# Peripherials.net
KiCad netlist of a schematic drawn in Altium Designer
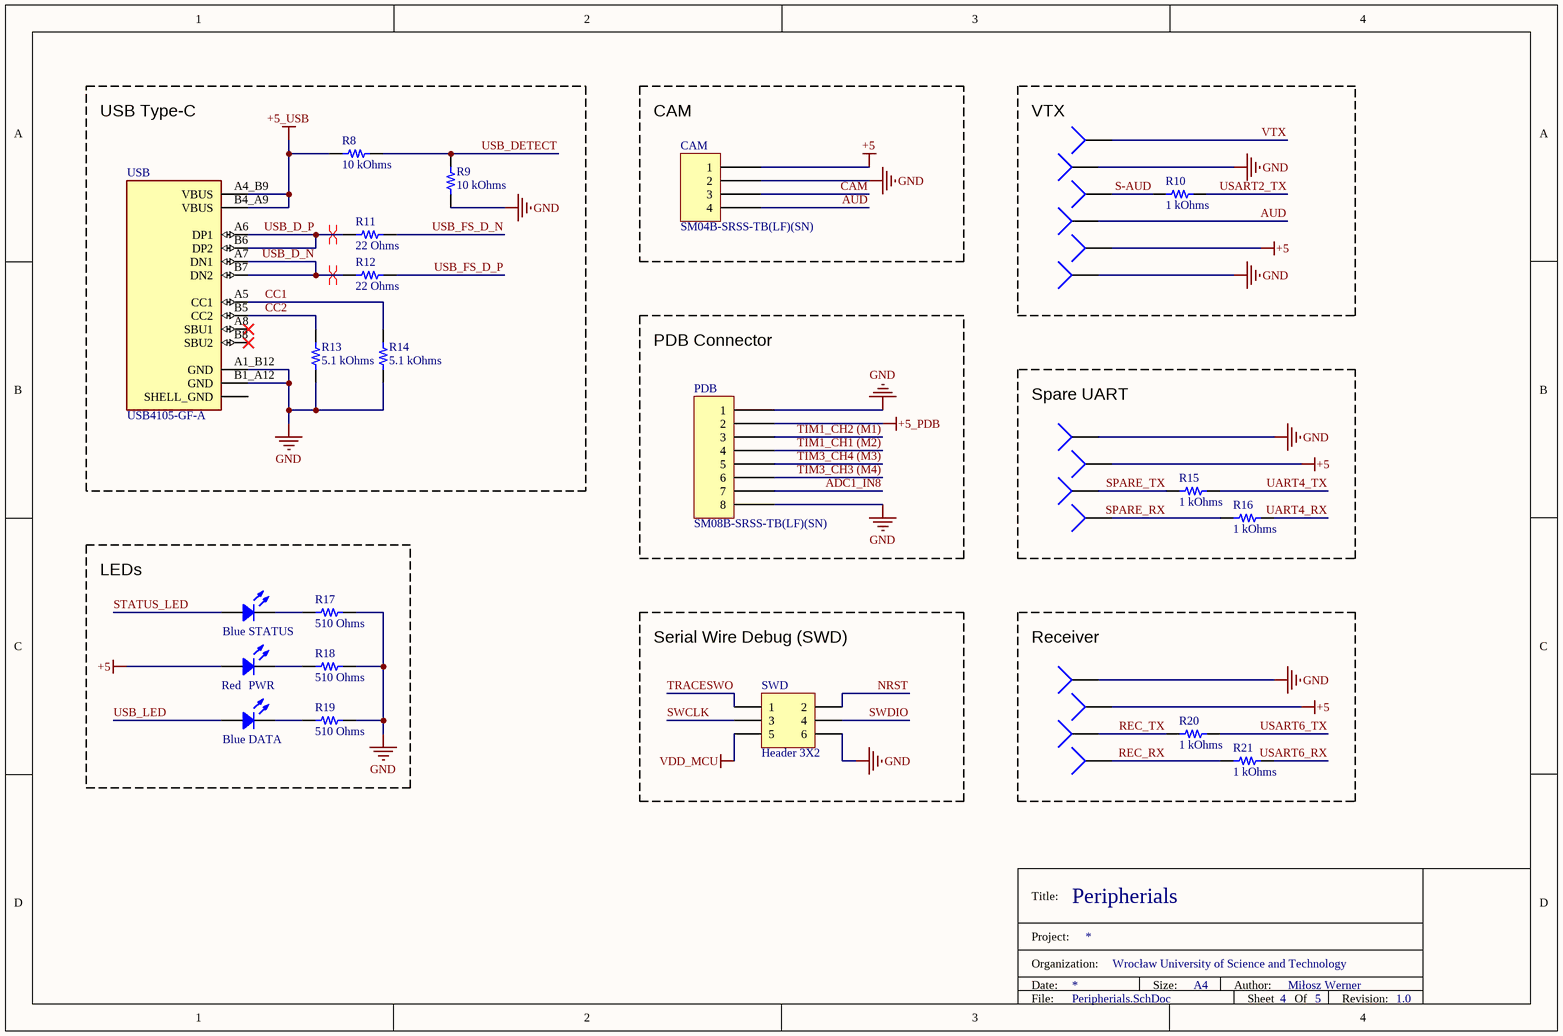
[diagram p0: Peripherials.SchDoc]

(export (version "E")
  (design (tool "Eeschema 10.0.6"))
  (components
    (comp (ref "CAM")
      (value "SM04B-SRSS-TB(LF)(SN)")
      (footprint "JST SM04B-SRSS-TB")
      (description "CONN HEADER SMD R/A 4POS 1MM")
      (fields (field (name "MANUFACTURER") "JST Sales America Inc."))
      (libsource (lib "Celestial Altium Library - altium_library") (part "4 Pin"))
    )
    (comp (ref "DATA")
      (value "Blue")
      (footprint "LED 0603_1608 BLUE")
      (description "LED BLUE CLEAR 0603 SMD")
      (fields (field (name "PART NUMBER") "QBLP601-IB") (field (name "MANUFACTURER") "QT Brightek (QTB)"))
      (libsource (lib "Celestial Altium Library - altium_library") (part "LED"))
    )
    (comp (ref "J1")
      (value "Socket")
      (footprint "PIN1")
      (fields (field (name "PUBLISHER") "Altium Limited"))
      (libsource (lib "Miscellaneous Connectors") (part "Socket"))
    )
    (comp (ref "J2")
      (value "Socket")
      (footprint "PIN1")
      (fields (field (name "PUBLISHER") "Altium Limited"))
      (libsource (lib "Miscellaneous Connectors") (part "Socket"))
    )
    (comp (ref "J3")
      (value "Socket")
      (footprint "PIN1")
      (fields (field (name "PUBLISHER") "Altium Limited"))
      (libsource (lib "Miscellaneous Connectors") (part "Socket"))
    )
    (comp (ref "J4")
      (value "Socket")
      (footprint "PIN1")
      (fields (field (name "PUBLISHER") "Altium Limited"))
      (libsource (lib "Miscellaneous Connectors") (part "Socket"))
    )
    (comp (ref "J5")
      (value "Socket")
      (footprint "PIN1")
      (fields (field (name "PUBLISHER") "Altium Limited"))
      (libsource (lib "Miscellaneous Connectors") (part "Socket"))
    )
    (comp (ref "J6")
      (value "Socket")
      (footprint "PIN1")
      (fields (field (name "PUBLISHER") "Altium Limited"))
      (libsource (lib "Miscellaneous Connectors") (part "Socket"))
    )
    (comp (ref "J7")
      (value "Socket")
      (footprint "PIN1")
      (fields (field (name "PUBLISHER") "Altium Limited"))
      (libsource (lib "Miscellaneous Connectors") (part "Socket"))
    )
    (comp (ref "J8")
      (value "Socket")
      (footprint "PIN1")
      (fields (field (name "PUBLISHER") "Altium Limited"))
      (libsource (lib "Miscellaneous Connectors") (part "Socket"))
    )
    (comp (ref "J9")
      (value "Socket")
      (footprint "PIN1")
      (fields (field (name "PUBLISHER") "Altium Limited"))
      (libsource (lib "Miscellaneous Connectors") (part "Socket"))
    )
    (comp (ref "J10")
      (value "Socket")
      (footprint "PIN1")
      (fields (field (name "PUBLISHER") "Altium Limited"))
      (libsource (lib "Miscellaneous Connectors") (part "Socket"))
    )
    (comp (ref "J11")
      (value "Socket")
      (footprint "PIN1")
      (fields (field (name "PUBLISHER") "Altium Limited"))
      (libsource (lib "Miscellaneous Connectors") (part "Socket"))
    )
    (comp (ref "J12")
      (value "Socket")
      (footprint "PIN1")
      (fields (field (name "PUBLISHER") "Altium Limited"))
      (libsource (lib "Miscellaneous Connectors") (part "Socket"))
    )
    (comp (ref "J13")
      (value "Socket")
      (footprint "PIN1")
      (fields (field (name "PUBLISHER") "Altium Limited"))
      (libsource (lib "Miscellaneous Connectors") (part "Socket"))
    )
    (comp (ref "J14")
      (value "Socket")
      (footprint "PIN1")
      (fields (field (name "PUBLISHER") "Altium Limited"))
      (libsource (lib "Miscellaneous Connectors") (part "Socket"))
    )
    (comp (ref "PDB")
      (value "SM08B-SRSS-TB(LF)(SN)")
      (footprint "JST SM08B-SRSS-TB")
      (description "CONN HEADER SMD R/A 8POS 1MM")
      (fields (field (name "MANUFACTURER") "JST Sales America Inc."))
      (libsource (lib "Celestial Altium Library - altium_library") (part "8 Pin"))
    )
    (comp (ref "PWR")
      (value "Red")
      (footprint "LED 0603_1608 RED")
      (description "LED RED CLEAR 0603 SMD")
      (fields (field (name "PART NUMBER") "QBLP601-R") (field (name "MANUFACTURER") "QT Brightek (QTB)"))
      (libsource (lib "Celestial Altium Library - altium_library") (part "LED"))
    )
    (comp (ref "R8")
      (value "10 kOhms")
      (footprint "RES 0603_1608")
      (description "RES 10K OHM 0.1% 1/5W 0603")
      (fields
        (field (name "PART NUMBER") "RS73F1JTTD1002B")
        (field (name "MANUFACTURER") "KOA Speer Electronics, Inc.")
      )
      (libsource (lib "Celestial Altium Library - altium_library") (part "Resistor"))
    )
    (comp (ref "R9")
      (value "10 kOhms")
      (footprint "RES 0603_1608")
      (description "RES 10K OHM 0.1% 1/5W 0603")
      (fields
        (field (name "PART NUMBER") "RS73F1JTTD1002B")
        (field (name "MANUFACTURER") "KOA Speer Electronics, Inc.")
      )
      (libsource (lib "Celestial Altium Library - altium_library") (part "Resistor"))
    )
    (comp (ref "R10")
      (value "1 kOhms")
      (footprint "RES 0603_1608")
      (description "RES 1K OHM 1% 1/5W 0603")
      (fields
        (field (name "PART NUMBER") "SG73S1JTTD1001F")
        (field (name "MANUFACTURER") "KOA Speer Electronics, Inc.")
      )
      (libsource (lib "Celestial Altium Library - altium_library") (part "Resistor"))
    )
    (comp (ref "R11")
      (value "22 Ohms")
      (footprint "RES 0603_1608")
      (description "RES 22 OHM 1% 1/10W 0603")
      (fields
        (field (name "PART NUMBER") "RMCF0603FT22R0")
        (field (name "MANUFACTURER") "Stackpole Electronics Inc")
      )
      (libsource (lib "Celestial Altium Library - altium_library") (part "Resistor"))
    )
    (comp (ref "R12")
      (value "22 Ohms")
      (footprint "RES 0603_1608")
      (description "RES 22 OHM 1% 1/10W 0603")
      (fields
        (field (name "PART NUMBER") "RMCF0603FT22R0")
        (field (name "MANUFACTURER") "Stackpole Electronics Inc")
      )
      (libsource (lib "Celestial Altium Library - altium_library") (part "Resistor"))
    )
    (comp (ref "R13")
      (value "5.1 kOhms")
      (footprint "RES 0603_1608")
      (description "RES 5.1 KOHM 1% 1/10W 0603")
      (fields
        (field (name "PART NUMBER") "RK73H1JRTTD5101F")
        (field (name "MANUFACTURER") "KOA Speer Electronics, Inc.")
      )
      (libsource (lib "Celestial Altium Library - altium_library") (part "Resistor"))
    )
    (comp (ref "R14")
      (value "5.1 kOhms")
      (footprint "RES 0603_1608")
      (description "RES 5.1 KOHM 1% 1/10W 0603")
      (fields
        (field (name "PART NUMBER") "RK73H1JRTTD5101F")
        (field (name "MANUFACTURER") "KOA Speer Electronics, Inc.")
      )
      (libsource (lib "Celestial Altium Library - altium_library") (part "Resistor"))
    )
    (comp (ref "R15")
      (value "1 kOhms")
      (footprint "RES 0603_1608")
      (description "RES 1K OHM 1% 1/5W 0603")
      (fields
        (field (name "PART NUMBER") "SG73S1JTTD1001F")
        (field (name "MANUFACTURER") "KOA Speer Electronics, Inc.")
      )
      (libsource (lib "Celestial Altium Library - altium_library") (part "Resistor"))
    )
    (comp (ref "R16")
      (value "1 kOhms")
      (footprint "RES 0603_1608")
      (description "RES 1K OHM 1% 1/5W 0603")
      (fields
        (field (name "PART NUMBER") "SG73S1JTTD1001F")
        (field (name "MANUFACTURER") "KOA Speer Electronics, Inc.")
      )
      (libsource (lib "Celestial Altium Library - altium_library") (part "Resistor"))
    )
    (comp (ref "R17")
      (value "510 Ohms")
      (footprint "RES 0603_1608")
      (description "RES 510 OHM 5% 1/8W 0603")
      (fields
        (field (name "PART NUMBER") "RK73B1JTTD511J")
        (field (name "MANUFACTURER") "KOA Speer Electronics, Inc.")
      )
      (libsource (lib "Celestial Altium Library - altium_library") (part "Resistor"))
    )
    (comp (ref "R18")
      (value "510 Ohms")
      (footprint "RES 0603_1608")
      (description "RES 510 OHM 5% 1/8W 0603")
      (fields
        (field (name "PART NUMBER") "RK73B1JTTD511J")
        (field (name "MANUFACTURER") "KOA Speer Electronics, Inc.")
      )
      (libsource (lib "Celestial Altium Library - altium_library") (part "Resistor"))
    )
    (comp (ref "R19")
      (value "510 Ohms")
      (footprint "RES 0603_1608")
      (description "RES 510 OHM 5% 1/8W 0603")
      (fields
        (field (name "PART NUMBER") "RK73B1JTTD511J")
        (field (name "MANUFACTURER") "KOA Speer Electronics, Inc.")
      )
      (libsource (lib "Celestial Altium Library - altium_library") (part "Resistor"))
    )
    (comp (ref "R20")
      (value "1 kOhms")
      (footprint "RES 0603_1608")
      (description "RES 1K OHM 1% 1/5W 0603")
      (fields
        (field (name "PART NUMBER") "SG73S1JTTD1001F")
        (field (name "MANUFACTURER") "KOA Speer Electronics, Inc.")
      )
      (libsource (lib "Celestial Altium Library - altium_library") (part "Resistor"))
    )
    (comp (ref "R21")
      (value "1 kOhms")
      (footprint "RES 0603_1608")
      (description "RES 1K OHM 1% 1/5W 0603")
      (fields
        (field (name "PART NUMBER") "SG73S1JTTD1001F")
        (field (name "MANUFACTURER") "KOA Speer Electronics, Inc.")
      )
      (libsource (lib "Celestial Altium Library - altium_library") (part "Resistor"))
    )
    (comp (ref "STATUS")
      (value "Blue")
      (footprint "LED 0603_1608 BLUE")
      (description "LED BLUE CLEAR 0603 SMD")
      (fields (field (name "PART NUMBER") "QBLP601-IB") (field (name "MANUFACTURER") "QT Brightek (QTB)"))
      (libsource (lib "Celestial Altium Library - altium_library") (part "LED"))
    )
    (comp (ref "SWD")
      (value "Header 3X2")
      (footprint "HDR2X3")
      (description "Header, 3-Pin, Dual row")
      (fields (field (name "PUBLISHER") "Altium Limited"))
      (libsource (lib "Miscellaneous Connectors") (part "Header 3X2"))
    )
    (comp (ref "USB")
      (value "USB4105-GF-A")
      (footprint "USB4105-GF-A:GCT_USB4105-GF-A")
      (fields (field (name "MF") "{'manufacturer': u'GCT'}"))
      (libsource (lib "USB4105-GF-A") (part "USB4105-GF-A"))
    )
  )
  (nets
    (net (code "1") (name "+5") (class "Default")
      (node (ref "CAM") (pin "1") (pinfunction "1_1") (pintype "passive"))
      (node (ref "J12") (pin "1") (pinfunction "1_1") (pintype "passive"))
      (node (ref "J5") (pin "1") (pinfunction "1_1") (pintype "passive"))
      (node (ref "J8") (pin "1") (pinfunction "1_1") (pintype "passive"))
      (node (ref "PWR") (pin "1") (pinfunction "1_1") (pintype "passive"))
    )
    (net (code "2") (name "+5_PDB") (class "Default")
      (node (ref "PDB") (pin "2") (pinfunction "2_2") (pintype "passive"))
    )
    (net (code "3") (name "+5_USB") (class "Default")
      (node (ref "R8") (pin "2") (pinfunction "2_2") (pintype "passive"))
      (node (ref "USB") (pin "A4_B9") (pinfunction "VBUS_A4_B9") (pintype "power_in"))
      (node (ref "USB") (pin "B4_A9") (pinfunction "VBUS_B4_A9") (pintype "power_in"))
    )
    (net (code "4") (name "/ADC1_IN8") (class "Default")
      (node (ref "PDB") (pin "7") (pinfunction "7_7") (pintype "passive"))
    )
    (net (code "5") (name "/AUD") (class "Default")
      (node (ref "CAM") (pin "4") (pinfunction "4_4") (pintype "passive"))
      (node (ref "J4") (pin "1") (pinfunction "1_1") (pintype "passive"))
    )
    (net (code "6") (name "/CAM") (class "Default")
      (node (ref "CAM") (pin "3") (pinfunction "3_3") (pintype "passive"))
    )
    (net (code "7") (name "/CC1") (class "Default")
      (node (ref "R14") (pin "1") (pinfunction "1_1") (pintype "passive"))
      (node (ref "USB") (pin "A5") (pinfunction "CC1_A5") (pintype "bidirectional"))
    )
    (net (code "8") (name "/CC2") (class "Default")
      (node (ref "R13") (pin "1") (pinfunction "1_1") (pintype "passive"))
      (node (ref "USB") (pin "B5") (pinfunction "CC2_B5") (pintype "bidirectional"))
    )
    (net (code "9") (name "/NRST") (class "Default")
      (node (ref "SWD") (pin "2") (pinfunction "2_2") (pintype "passive"))
    )
    (net (code "10") (name "/REC_RX") (class "Default")
      (node (ref "J14") (pin "1") (pinfunction "1_1") (pintype "passive"))
      (node (ref "R21") (pin "1") (pinfunction "1_1") (pintype "passive"))
    )
    (net (code "11") (name "/REC_TX") (class "Default")
      (node (ref "J13") (pin "1") (pinfunction "1_1") (pintype "passive"))
      (node (ref "R20") (pin "1") (pinfunction "1_1") (pintype "passive"))
    )
    (net (code "12") (name "/S-AUD") (class "Default")
      (node (ref "J3") (pin "1") (pinfunction "1_1") (pintype "passive"))
      (node (ref "R10") (pin "1") (pinfunction "1_1") (pintype "passive"))
    )
    (net (code "13") (name "/SPARE_RX") (class "Default")
      (node (ref "J10") (pin "1") (pinfunction "1_1") (pintype "passive"))
      (node (ref "R16") (pin "1") (pinfunction "1_1") (pintype "passive"))
    )
    (net (code "14") (name "/SPARE_TX") (class "Default")
      (node (ref "J9") (pin "1") (pinfunction "1_1") (pintype "passive"))
      (node (ref "R15") (pin "1") (pinfunction "1_1") (pintype "passive"))
    )
    (net (code "15") (name "/STATUS_LED") (class "Default")
      (node (ref "STATUS") (pin "1") (pinfunction "1_1") (pintype "passive"))
    )
    (net (code "16") (name "/SWCLK") (class "Default")
      (node (ref "SWD") (pin "3") (pinfunction "3_3") (pintype "passive"))
    )
    (net (code "17") (name "/SWDIO") (class "Default")
      (node (ref "SWD") (pin "4") (pinfunction "4_4") (pintype "passive"))
    )
    (net (code "18") (name "/TIM1_CH1 (M2)") (class "Default")
      (node (ref "PDB") (pin "4") (pinfunction "4_4") (pintype "passive"))
    )
    (net (code "19") (name "/TIM1_CH2 (M1)") (class "Default")
      (node (ref "PDB") (pin "3") (pinfunction "3_3") (pintype "passive"))
    )
    (net (code "20") (name "/TIM3_CH3 (M4)") (class "Default")
      (node (ref "PDB") (pin "6") (pinfunction "6_6") (pintype "passive"))
    )
    (net (code "21") (name "/TIM3_CH4 (M3)") (class "Default")
      (node (ref "PDB") (pin "5") (pinfunction "5_5") (pintype "passive"))
    )
    (net (code "22") (name "/TRACESWO") (class "Default")
      (node (ref "SWD") (pin "1") (pinfunction "1_1") (pintype "passive"))
    )
    (net (code "23") (name "/UART4_RX") (class "Default")
      (node (ref "R16") (pin "2") (pinfunction "2_2") (pintype "passive"))
    )
    (net (code "24") (name "/UART4_TX") (class "Default")
      (node (ref "R15") (pin "2") (pinfunction "2_2") (pintype "passive"))
    )
    (net (code "25") (name "/USART2_TX") (class "Default")
      (node (ref "R10") (pin "2") (pinfunction "2_2") (pintype "passive"))
    )
    (net (code "26") (name "/USART6_RX") (class "Default")
      (node (ref "R21") (pin "2") (pinfunction "2_2") (pintype "passive"))
    )
    (net (code "27") (name "/USART6_TX") (class "Default")
      (node (ref "R20") (pin "2") (pinfunction "2_2") (pintype "passive"))
    )
    (net (code "28") (name "/USB_DETECT") (class "Default")
      (node (ref "R8") (pin "1") (pinfunction "1_1") (pintype "passive"))
      (node (ref "R9") (pin "1") (pinfunction "1_1") (pintype "passive"))
    )
    (net (code "29") (name "/USB_D_N") (class "Default")
      (node (ref "R12") (pin "1") (pinfunction "1_1") (pintype "passive"))
      (node (ref "USB") (pin "A7") (pinfunction "DN1_A7") (pintype "bidirectional"))
      (node (ref "USB") (pin "B7") (pinfunction "DN2_B7") (pintype "bidirectional"))
    )
    (net (code "30") (name "/USB_D_P") (class "Default")
      (node (ref "R11") (pin "1") (pinfunction "1_1") (pintype "passive"))
      (node (ref "USB") (pin "A6") (pinfunction "DP1_A6") (pintype "bidirectional"))
      (node (ref "USB") (pin "B6") (pinfunction "DP2_B6") (pintype "bidirectional"))
    )
    (net (code "31") (name "/USB_FS_D_N") (class "Default")
      (node (ref "R11") (pin "2") (pinfunction "2_2") (pintype "passive"))
    )
    (net (code "32") (name "/USB_FS_D_P") (class "Default")
      (node (ref "R12") (pin "2") (pinfunction "2_2") (pintype "passive"))
    )
    (net (code "33") (name "/USB_LED") (class "Default")
      (node (ref "DATA") (pin "1") (pinfunction "1_1") (pintype "passive"))
    )
    (net (code "34") (name "/VTX") (class "Default")
      (node (ref "J1") (pin "1") (pinfunction "1_1") (pintype "passive"))
    )
    (net (code "35") (name "GND") (class "Default")
      (node (ref "CAM") (pin "2") (pinfunction "2_2") (pintype "passive"))
      (node (ref "J11") (pin "1") (pinfunction "1_1") (pintype "passive"))
      (node (ref "J2") (pin "1") (pinfunction "1_1") (pintype "passive"))
      (node (ref "J6") (pin "1") (pinfunction "1_1") (pintype "passive"))
      (node (ref "J7") (pin "1") (pinfunction "1_1") (pintype "passive"))
      (node (ref "PDB") (pin "1") (pinfunction "1_1") (pintype "passive"))
      (node (ref "PDB") (pin "8") (pinfunction "8_8") (pintype "passive"))
      (node (ref "R13") (pin "2") (pinfunction "2_2") (pintype "passive"))
      (node (ref "R14") (pin "2") (pinfunction "2_2") (pintype "passive"))
      (node (ref "R17") (pin "2") (pinfunction "2_2") (pintype "passive"))
      (node (ref "R18") (pin "2") (pinfunction "2_2") (pintype "passive"))
      (node (ref "R19") (pin "2") (pinfunction "2_2") (pintype "passive"))
      (node (ref "R9") (pin "2") (pinfunction "2_2") (pintype "passive"))
      (node (ref "SWD") (pin "6") (pinfunction "6_6") (pintype "passive"))
      (node (ref "USB") (pin "A1_B12") (pinfunction "GND_A1_B12") (pintype "power_in"))
      (node (ref "USB") (pin "B1_A12") (pinfunction "GND_B1_A12") (pintype "power_in"))
    )
    (net (code "36") (name "Net-(DATA-Pad2)") (class "Default")
      (node (ref "DATA") (pin "2") (pinfunction "2_2") (pintype "passive"))
      (node (ref "R19") (pin "1") (pinfunction "1_1") (pintype "passive"))
    )
    (net (code "37") (name "Net-(PWR-Pad2)") (class "Default")
      (node (ref "PWR") (pin "2") (pinfunction "2_2") (pintype "passive"))
      (node (ref "R18") (pin "1") (pinfunction "1_1") (pintype "passive"))
    )
    (net (code "38") (name "Net-(R17-Pad1)") (class "Default")
      (node (ref "R17") (pin "1") (pinfunction "1_1") (pintype "passive"))
      (node (ref "STATUS") (pin "2") (pinfunction "2_2") (pintype "passive"))
    )
    (net (code "39") (name "VDD_MCU") (class "Default")
      (node (ref "SWD") (pin "5") (pinfunction "5_5") (pintype "passive"))
    )
    (net (code "40") (name "unconnected-(USB-SBU1-PadA8)") (class "Default")
      (node (ref "USB") (pin "A8") (pinfunction "SBU1_A8") (pintype "bidirectional+no_connect"))
    )
    (net (code "41") (name "unconnected-(USB-SBU2-PadB8)") (class "Default")
      (node (ref "USB") (pin "B8") (pinfunction "SBU2_B8") (pintype "bidirectional+no_connect"))
    )
    (net (code "42") (name "unconnected-(USB-SHELL_GND-Pad)") (class "Default")
      (node (ref "USB") (pin "") (pinfunction "SHELL_GND_") (pintype "power_in"))
    )
  )
)
